# SCH_SHOC.net
KiCad netlist of a schematic drawn in EasyEDA
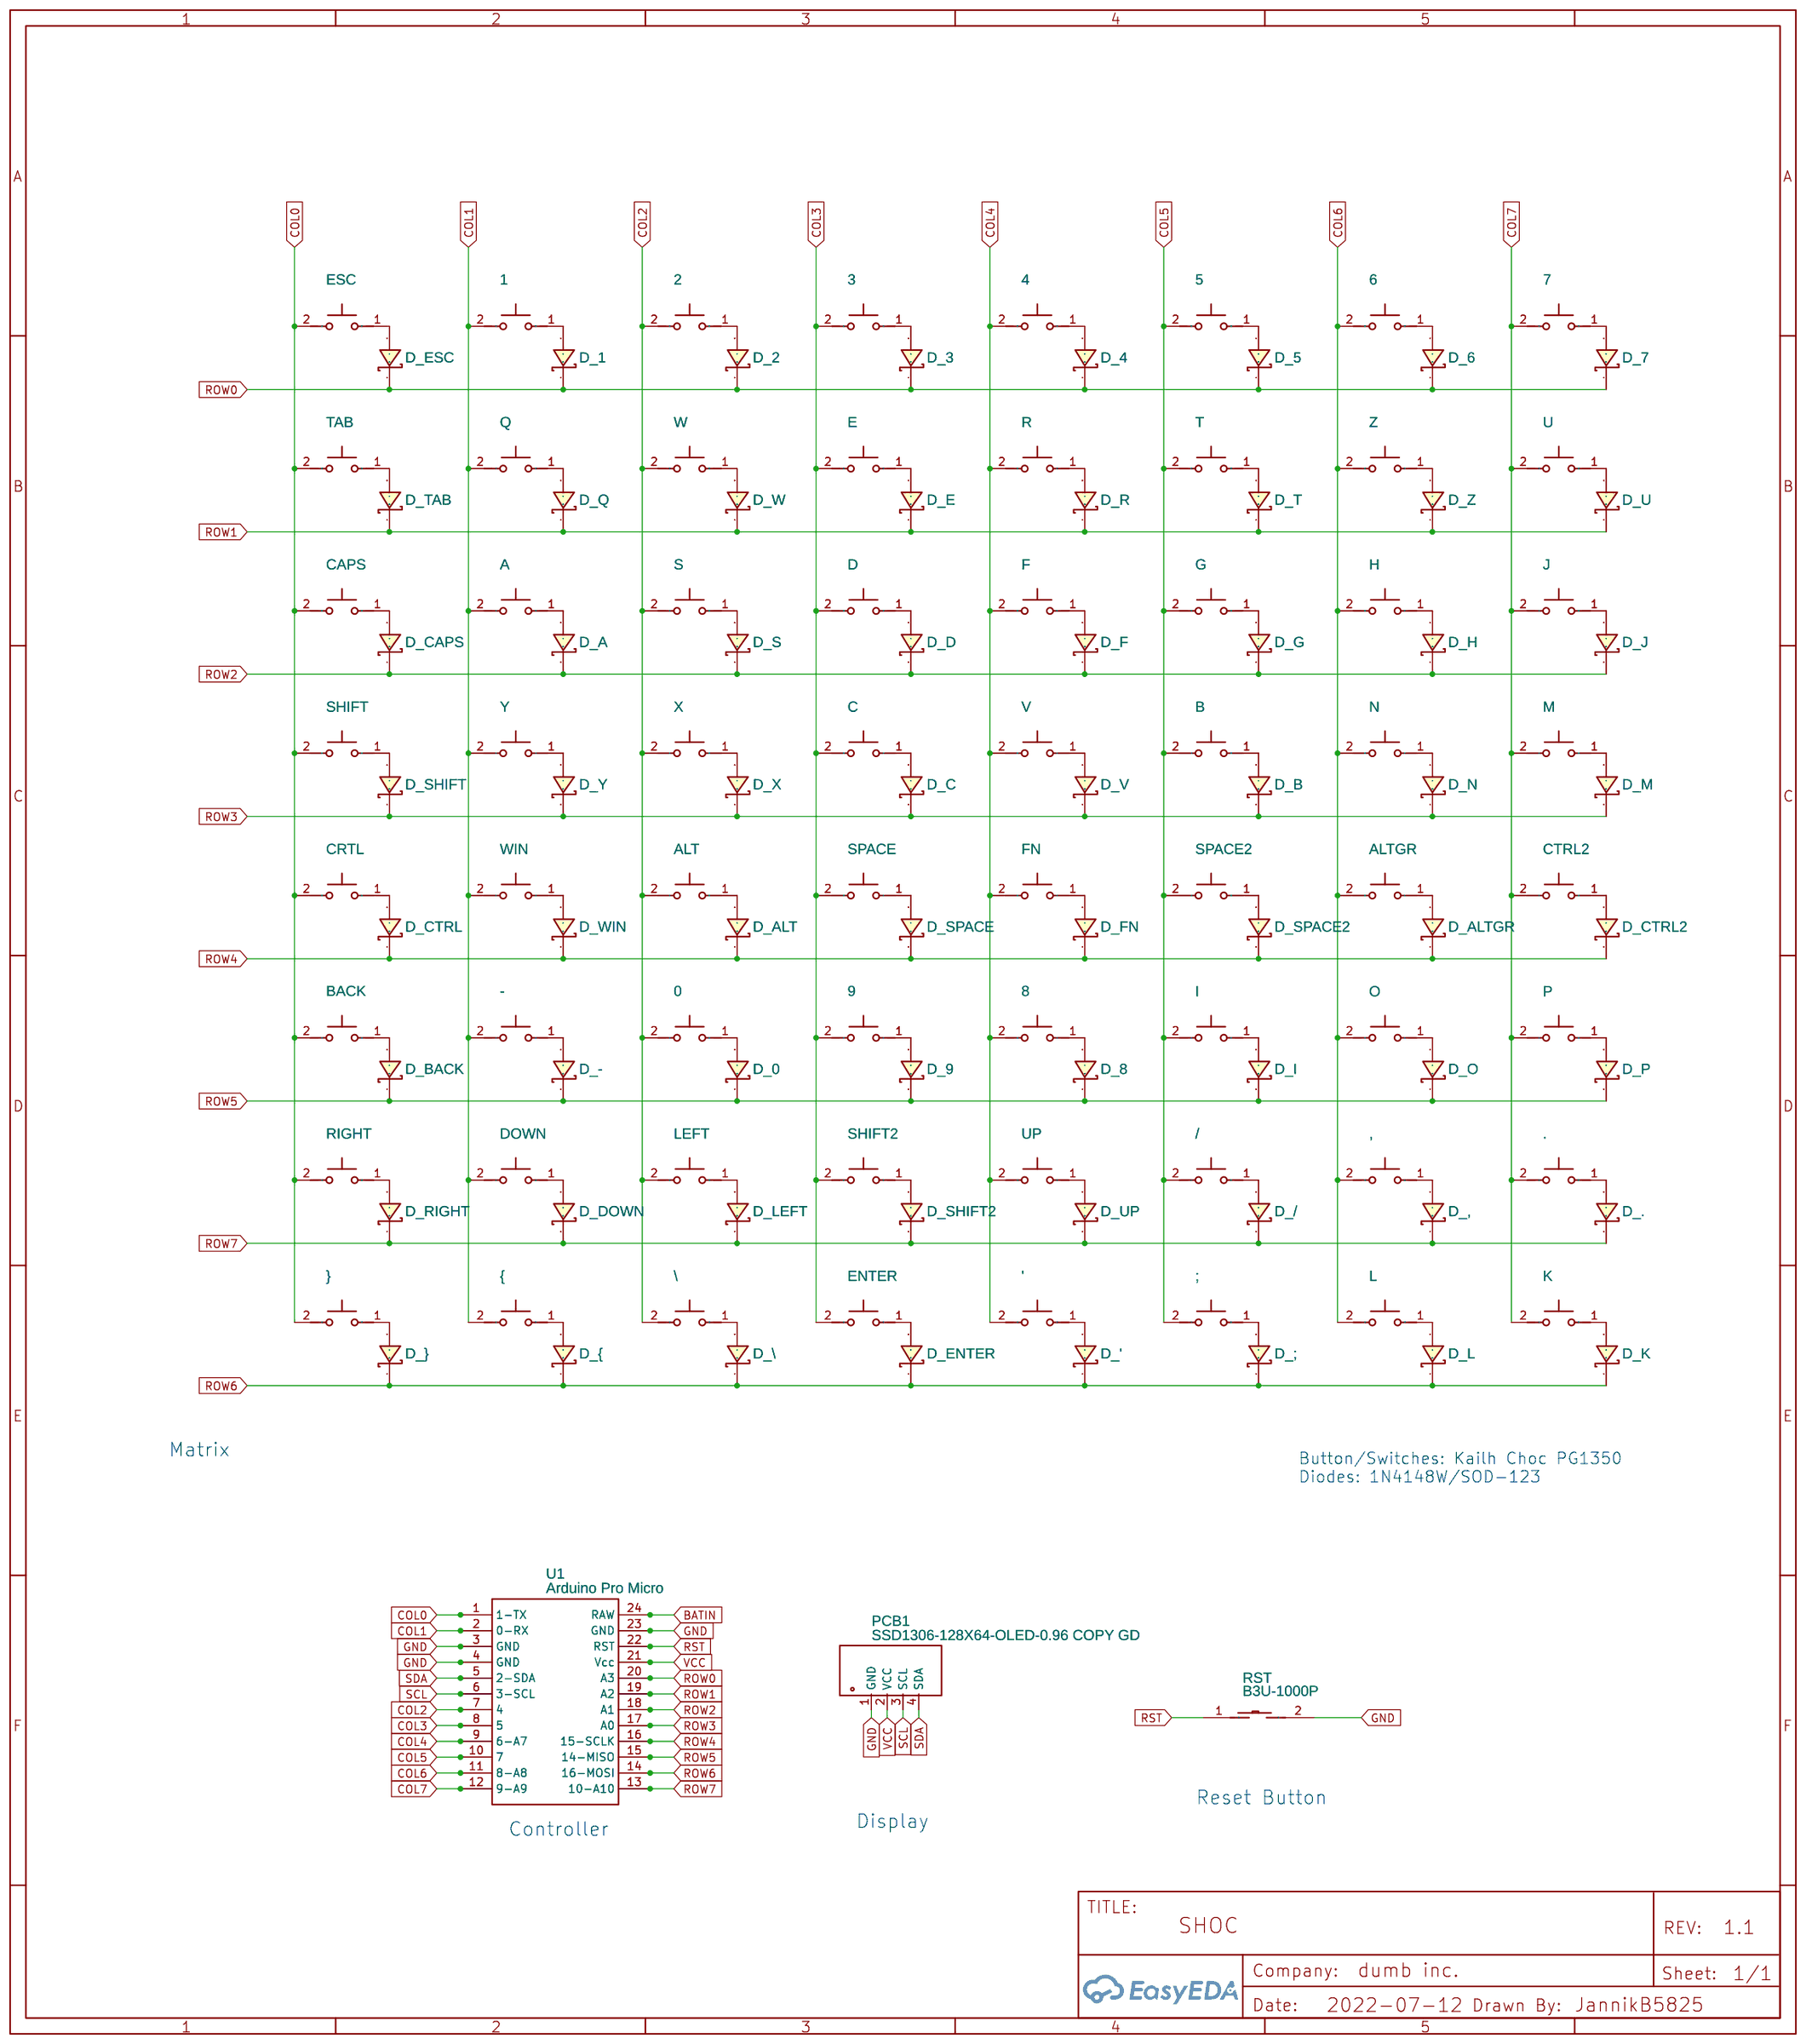
[diagram p0: schematic sheet]

(export (version "E")
  (design (tool "Eeschema 10.0.6"))
  (components
    (comp (ref "'")
      (value "PG1350")
      (fields
        (field (name "BOM_Manufacturer Part") "CPG135001D02")
        (field (name "BOM_Supplier Part") "C400230")
      )
      (libsource (lib "") (part "PG1350_35"))
    )
    (comp (ref ",")
      (value "PG1350")
      (fields
        (field (name "BOM_Manufacturer Part") "CPG135001D02")
        (field (name "BOM_Supplier Part") "C400230")
      )
      (libsource (lib "") (part "PG1350_47"))
    )
    (comp (ref "-")
      (value "PG1350")
      (fields
        (field (name "BOM_Manufacturer Part") "CPG135001D02")
        (field (name "BOM_Supplier Part") "C400230")
      )
      (libsource (lib "") (part "PG1350_14"))
    )
    (comp (ref ".")
      (value "PG1350")
      (fields
        (field (name "BOM_Manufacturer Part") "CPG135001D02")
        (field (name "BOM_Supplier Part") "C400230")
      )
      (libsource (lib "") (part "PG1350_38"))
    )
    (comp (ref "/")
      (value "PG1350")
      (fields
        (field (name "BOM_Manufacturer Part") "CPG135001D02")
        (field (name "BOM_Supplier Part") "C400230")
      )
      (libsource (lib "") (part "PG1350_29"))
    )
    (comp (ref "0")
      (value "PG1350")
      (fields
        (field (name "BOM_Manufacturer Part") "CPG135001D02")
        (field (name "BOM_Supplier Part") "C400230")
      )
      (libsource (lib "") (part "PG1350_15"))
    )
    (comp (ref "1")
      (value "PG1350")
      (fields
        (field (name "BOM_Manufacturer Part") "CPG135001D02")
        (field (name "BOM_Supplier Part") "C400230")
      )
      (libsource (lib "") (part "PG1350_15"))
    )
    (comp (ref "2")
      (value "PG1350")
      (fields
        (field (name "BOM_Manufacturer Part") "CPG135001D02")
        (field (name "BOM_Supplier Part") "C400230")
      )
      (libsource (lib "") (part "PG1350_15"))
    )
    (comp (ref "3")
      (value "PG1350")
      (fields
        (field (name "BOM_Manufacturer Part") "CPG135001D02")
        (field (name "BOM_Supplier Part") "C400230")
      )
      (libsource (lib "") (part "PG1350_15"))
    )
    (comp (ref "4")
      (value "PG1350")
      (fields
        (field (name "BOM_Manufacturer Part") "CPG135001D02")
        (field (name "BOM_Supplier Part") "C400230")
      )
      (libsource (lib "") (part "PG1350_15"))
    )
    (comp (ref "5")
      (value "PG1350")
      (fields
        (field (name "BOM_Manufacturer Part") "CPG135001D02")
        (field (name "BOM_Supplier Part") "C400230")
      )
      (libsource (lib "") (part "PG1350_15"))
    )
    (comp (ref "6")
      (value "PG1350")
      (fields
        (field (name "BOM_Manufacturer Part") "CPG135001D02")
        (field (name "BOM_Supplier Part") "C400230")
      )
      (libsource (lib "") (part "PG1350_15"))
    )
    (comp (ref "7")
      (value "PG1350")
      (fields
        (field (name "BOM_Manufacturer Part") "CPG135001D02")
        (field (name "BOM_Supplier Part") "C400230")
      )
      (libsource (lib "") (part "PG1350_15"))
    )
    (comp (ref "8")
      (value "PG1350")
      (fields
        (field (name "BOM_Manufacturer Part") "CPG135001D02")
        (field (name "BOM_Supplier Part") "C400230")
      )
      (libsource (lib "") (part "PG1350_15"))
    )
    (comp (ref "9")
      (value "PG1350")
      (fields
        (field (name "BOM_Manufacturer Part") "CPG135001D02")
        (field (name "BOM_Supplier Part") "C400230")
      )
      (libsource (lib "") (part "PG1350_15"))
    )
    (comp (ref ";")
      (value "PG1350")
      (fields
        (field (name "BOM_Manufacturer Part") "CPG135001D02")
        (field (name "BOM_Supplier Part") "C400230")
      )
      (libsource (lib "") (part "PG1350_20"))
    )
    (comp (ref "A")
      (value "PG1350")
      (fields (field (name "BOM_Manufacturer Part") "?"))
      (libsource (lib "") (part "Unknown_205_-1510"))
    )
    (comp (ref "ALT")
      (value "PG1350")
      (fields
        (field (name "BOM_Manufacturer Part") "CPG135001D02")
        (field (name "BOM_Supplier Part") "C400230")
      )
      (libsource (lib "") (part "PG1350_33"))
    )
    (comp (ref "ALTGR")
      (value "PG1350")
      (fields
        (field (name "BOM_Manufacturer Part") "CPG135001D02")
        (field (name "BOM_Supplier Part") "C400230")
      )
      (libsource (lib "") (part "PG1350_24"))
    )
    (comp (ref "B")
      (value "PG1350")
      (fields
        (field (name "BOM_Manufacturer Part") "CPG135001D02")
        (field (name "BOM_Supplier Part") "C400230")
      )
      (libsource (lib "") (part "PG1350_31"))
    )
    (comp (ref "BACK")
      (value "PG1350")
      (fields
        (field (name "BOM_Manufacturer Part") "CPG135001D02")
        (field (name "BOM_Supplier Part") "C400230")
      )
      (libsource (lib "") (part "PG1350_18"))
    )
    (comp (ref "C")
      (value "PG1350")
      (fields
        (field (name "BOM_Manufacturer Part") "CPG135001D02")
        (field (name "BOM_Supplier Part") "C400230")
      )
      (libsource (lib "") (part "PG1350"))
    )
    (comp (ref "CAPS")
      (value "PG1350")
      (fields
        (field (name "BOM_Manufacturer Part") "CPG135001D02")
        (field (name "BOM_Supplier Part") "C400230")
      )
      (libsource (lib "") (part "PG1350_9"))
    )
    (comp (ref "CRTL")
      (value "PG1350")
      (fields
        (field (name "BOM_Manufacturer Part") "CPG135001D02")
        (field (name "BOM_Supplier Part") "C400230")
      )
      (libsource (lib "") (part "PG1350_19"))
    )
    (comp (ref "CTRL2")
      (value "PG1350")
      (fields
        (field (name "BOM_Manufacturer Part") "CPG135001D02")
        (field (name "BOM_Supplier Part") "C400230")
      )
      (libsource (lib "") (part "PG1350_41"))
    )
    (comp (ref "D")
      (value "PG1350")
      (fields
        (field (name "BOM_Manufacturer Part") "CPG135001D02")
        (field (name "BOM_Supplier Part") "C400230")
      )
      (libsource (lib "") (part "PG1350_8"))
    )
    (comp (ref "DOWN")
      (value "PG1350")
      (fields
        (field (name "BOM_Manufacturer Part") "CPG135001D02")
        (field (name "BOM_Supplier Part") "C400230")
      )
      (libsource (lib "") (part "PG1350_30"))
    )
    (comp (ref "D_'")
      (value "MBR2H200SFT3G")
      (fields (field (name "BOM_Supplier Part") "MBR2H200SFT3GOSCT-ND"))
      (libsource (lib "") (part "MBR2H200SFT3G_51"))
    )
    (comp (ref "D_,")
      (value "MBR2H200SFT3G")
      (fields (field (name "BOM_Supplier Part") "MBR2H200SFT3GOSCT-ND"))
      (libsource (lib "") (part "MBR2H200SFT3G_27"))
    )
    (comp (ref "D_-")
      (value "MBR2H200SFT3G")
      (fields (field (name "BOM_Supplier Part") "MBR2H200SFT3GOSCT-ND"))
      (libsource (lib "") (part "MBR2H200SFT3G_3"))
    )
    (comp (ref "D_.")
      (value "MBR2H200SFT3G")
      (fields (field (name "BOM_Supplier Part") "MBR2H200SFT3GOSCT-ND"))
      (libsource (lib "") (part "MBR2H200SFT3G_7"))
    )
    (comp (ref "D_/")
      (value "MBR2H200SFT3G")
      (fields (field (name "BOM_Supplier Part") "MBR2H200SFT3GOSCT-ND"))
      (libsource (lib "") (part "MBR2H200SFT3G_31"))
    )
    (comp (ref "D_0")
      (value "MBR2H200SFT3G")
      (fields (field (name "BOM_Supplier Part") "MBR2H200SFT3GOSCT-ND"))
      (libsource (lib "") (part "MBR2H200SFT3G_8"))
    )
    (comp (ref "D_1")
      (value "MBR2H200SFT3G")
      (fields (field (name "BOM_Supplier Part") "MBR2H200SFT3GOSCT-ND"))
      (libsource (lib "") (part "MBR2H200SFT3G_8"))
    )
    (comp (ref "D_2")
      (value "MBR2H200SFT3G")
      (fields (field (name "BOM_Supplier Part") "MBR2H200SFT3GOSCT-ND"))
      (libsource (lib "") (part "MBR2H200SFT3G_8"))
    )
    (comp (ref "D_3")
      (value "MBR2H200SFT3G")
      (fields (field (name "BOM_Supplier Part") "MBR2H200SFT3GOSCT-ND"))
      (libsource (lib "") (part "MBR2H200SFT3G_8"))
    )
    (comp (ref "D_4")
      (value "MBR2H200SFT3G")
      (fields (field (name "BOM_Supplier Part") "MBR2H200SFT3GOSCT-ND"))
      (libsource (lib "") (part "MBR2H200SFT3G_8"))
    )
    (comp (ref "D_5")
      (value "MBR2H200SFT3G")
      (fields (field (name "BOM_Supplier Part") "MBR2H200SFT3GOSCT-ND"))
      (libsource (lib "") (part "MBR2H200SFT3G_8"))
    )
    (comp (ref "D_6")
      (value "MBR2H200SFT3G")
      (fields (field (name "BOM_Supplier Part") "MBR2H200SFT3GOSCT-ND"))
      (libsource (lib "") (part "MBR2H200SFT3G_8"))
    )
    (comp (ref "D_7")
      (value "MBR2H200SFT3G")
      (fields (field (name "BOM_Supplier Part") "MBR2H200SFT3GOSCT-ND"))
      (libsource (lib "") (part "MBR2H200SFT3G_8"))
    )
    (comp (ref "D_8")
      (value "MBR2H200SFT3G")
      (fields (field (name "BOM_Supplier Part") "MBR2H200SFT3GOSCT-ND"))
      (libsource (lib "") (part "MBR2H200SFT3G_8"))
    )
    (comp (ref "D_9")
      (value "MBR2H200SFT3G")
      (fields (field (name "BOM_Supplier Part") "MBR2H200SFT3GOSCT-ND"))
      (libsource (lib "") (part "MBR2H200SFT3G_8"))
    )
    (comp (ref "D_;")
      (value "MBR2H200SFT3G")
      (fields (field (name "BOM_Supplier Part") "MBR2H200SFT3GOSCT-ND"))
      (libsource (lib "") (part "MBR2H200SFT3G_13"))
    )
    (comp (ref "D_A")
      (value "MBR2H200SFT3G")
      (fields (field (name "BOM_Supplier Part") "MBR2H200SFT3GOSCT-ND"))
      (libsource (lib "") (part "MBR2H200SFT3G_44"))
    )
    (comp (ref "D_ALT")
      (value "MBR2H200SFT3G")
      (fields (field (name "BOM_Supplier Part") "MBR2H200SFT3GOSCT-ND"))
      (libsource (lib "") (part "MBR2H200SFT3G_21"))
    )
    (comp (ref "D_ALTGR")
      (value "MBR2H200SFT3G")
      (fields (field (name "BOM_Supplier Part") "MBR2H200SFT3GOSCT-ND"))
      (libsource (lib "") (part "MBR2H200SFT3G_42"))
    )
    (comp (ref "D_B")
      (value "MBR2H200SFT3G")
      (fields (field (name "BOM_Supplier Part") "MBR2H200SFT3GOSCT-ND"))
      (libsource (lib "") (part "MBR2H200SFT3G_18"))
    )
    (comp (ref "D_BACK")
      (value "MBR2H200SFT3G")
      (fields (field (name "BOM_Supplier Part") "MBR2H200SFT3GOSCT-ND"))
      (libsource (lib "") (part "MBR2H200SFT3G_12"))
    )
    (comp (ref "D_C")
      (value "MBR2H200SFT3G")
      (fields (field (name "BOM_Supplier Part") "MBR2H200SFT3GOSCT-ND"))
      (libsource (lib "") (part "MBR2H200SFT3G_19"))
    )
    (comp (ref "D_CAPS")
      (value "MBR2H200SFT3G")
      (fields (field (name "BOM_Supplier Part") "MBR2H200SFT3GOSCT-ND"))
      (libsource (lib "") (part "MBR2H200SFT3G_24"))
    )
    (comp (ref "D_CTRL")
      (value "MBR2H200SFT3G")
      (fields (field (name "BOM_Supplier Part") "MBR2H200SFT3GOSCT-ND"))
      (libsource (lib "") (part "MBR2H200SFT3G_22"))
    )
    (comp (ref "D_CTRL2")
      (value "MBR2H200SFT3G")
      (fields (field (name "BOM_Supplier Part") "MBR2H200SFT3GOSCT-ND"))
      (libsource (lib "") (part "MBR2H200SFT3G_22"))
    )
    (comp (ref "D_D")
      (value "MBR2H200SFT3G")
      (fields (field (name "BOM_Supplier Part") "MBR2H200SFT3GOSCT-ND"))
      (libsource (lib "") (part "MBR2H200SFT3G_23"))
    )
    (comp (ref "D_DOWN")
      (value "MBR2H200SFT3G")
      (fields (field (name "BOM_Supplier Part") "MBR2H200SFT3GOSCT-ND"))
      (libsource (lib "") (part "MBR2H200SFT3G_36"))
    )
    (comp (ref "D_E")
      (value "MBR2H200SFT3G")
      (fields (field (name "BOM_Supplier Part") "MBR2H200SFT3GOSCT-ND"))
      (libsource (lib "") (part "MBR2H200SFT3G_45"))
    )
    (comp (ref "D_ENTER")
      (value "MBR2H200SFT3G")
      (fields (field (name "BOM_Supplier Part") "MBR2H200SFT3GOSCT-ND"))
      (libsource (lib "") (part "MBR2H200SFT3G_41"))
    )
    (comp (ref "D_ESC")
      (value "MBR2H200SFT3G")
      (fields (field (name "BOM_Supplier Part") "MBR2H200SFT3GOSCT-ND"))
      (libsource (lib "") (part "MBR2H200SFT3G_6"))
    )
    (comp (ref "D_F")
      (value "MBR2H200SFT3G")
      (fields (field (name "BOM_Supplier Part") "MBR2H200SFT3GOSCT-ND"))
      (libsource (lib "") (part "MBR2H200SFT3G_34"))
    )
    (comp (ref "D_FN")
      (value "MBR2H200SFT3G")
      (fields (field (name "BOM_Supplier Part") "MBR2H200SFT3GOSCT-ND"))
      (libsource (lib "") (part "MBR2H200SFT3G_26"))
    )
    (comp (ref "D_G")
      (value "MBR2H200SFT3G")
      (fields (field (name "BOM_Supplier Part") "MBR2H200SFT3GOSCT-ND"))
      (libsource (lib "") (part "MBR2H200SFT3G_16"))
    )
    (comp (ref "D_H")
      (value "MBR2H200SFT3G")
      (fields (field (name "BOM_Supplier Part") "MBR2H200SFT3GOSCT-ND"))
      (libsource (lib "") (part "MBR2H200SFT3G_43"))
    )
    (comp (ref "D_I")
      (value "MBR2H200SFT3G")
      (fields (field (name "BOM_Supplier Part") "MBR2H200SFT3GOSCT-ND"))
      (libsource (lib "") (part "MBR2H200SFT3G_10"))
    )
    (comp (ref "D_J")
      (value "MBR2H200SFT3G")
      (fields (field (name "BOM_Supplier Part") "MBR2H200SFT3GOSCT-ND"))
      (libsource (lib "") (part "MBR2H200SFT3G_15"))
    )
    (comp (ref "D_K")
      (value "MBR2H200SFT3G")
      (fields (field (name "BOM_Supplier Part") "MBR2H200SFT3GOSCT-ND"))
      (libsource (lib "") (part "MBR2H200SFT3G_37"))
    )
    (comp (ref "D_L")
      (value "MBR2H200SFT3G")
      (fields (field (name "BOM_Supplier Part") "MBR2H200SFT3GOSCT-ND"))
      (libsource (lib "") (part "MBR2H200SFT3G_20"))
    )
    (comp (ref "D_LEFT")
      (value "MBR2H200SFT3G")
      (fields (field (name "BOM_Supplier Part") "MBR2H200SFT3GOSCT-ND"))
      (libsource (lib "") (part "MBR2H200SFT3G_48"))
    )
    (comp (ref "D_M")
      (value "MBR2H200SFT3G")
      (fields (field (name "BOM_Supplier Part") "MBR2H200SFT3GOSCT-ND"))
      (libsource (lib "") (part "MBR2H200SFT3G_33"))
    )
    (comp (ref "D_N")
      (value "MBR2H200SFT3G")
      (fields (field (name "BOM_Supplier Part") "MBR2H200SFT3GOSCT-ND"))
      (libsource (lib "") (part "MBR2H200SFT3G_47"))
    )
    (comp (ref "D_O")
      (value "MBR2H200SFT3G")
      (fields (field (name "BOM_Supplier Part") "MBR2H200SFT3GOSCT-ND"))
      (libsource (lib "") (part "MBR2H200SFT3G_4"))
    )
    (comp (ref "D_P")
      (value "MBR2H200SFT3G")
      (fields (field (name "BOM_Supplier Part") "MBR2H200SFT3GOSCT-ND"))
      (libsource (lib "") (part "MBR2H200SFT3G_49"))
    )
    (comp (ref "D_Q")
      (value "MBR2H200SFT3G")
      (fields (field (name "BOM_Supplier Part") "MBR2H200SFT3GOSCT-ND"))
      (libsource (lib "") (part "MBR2H200SFT3G_11"))
    )
    (comp (ref "D_R")
      (value "MBR2H200SFT3G")
      (fields (field (name "BOM_Supplier Part") "MBR2H200SFT3GOSCT-ND"))
      (libsource (lib "") (part "MBR2H200SFT3G_29"))
    )
    (comp (ref "D_RIGHT")
      (value "MBR2H200SFT3G")
      (fields (field (name "BOM_Supplier Part") "MBR2H200SFT3GOSCT-ND"))
      (libsource (lib "") (part "MBR2H200SFT3G_14"))
    )
    (comp (ref "D_S")
      (value "MBR2H200SFT3G")
      (fields (field (name "BOM_Supplier Part") "MBR2H200SFT3GOSCT-ND"))
      (libsource (lib "") (part "MBR2H200SFT3G_28"))
    )
    (comp (ref "D_SHIFT")
      (value "MBR2H200SFT3G")
      (fields (field (name "BOM_Supplier Part") "MBR2H200SFT3GOSCT-ND"))
      (libsource (lib "") (part "MBR2H200SFT3G_25"))
    )
    (comp (ref "D_SHIFT2")
      (value "MBR2H200SFT3G")
      (fields (field (name "BOM_Supplier Part") "MBR2H200SFT3GOSCT-ND"))
      (libsource (lib "") (part "MBR2H200SFT3G_25"))
    )
    (comp (ref "D_SPACE")
      (value "MBR2H200SFT3G")
      (fields (field (name "BOM_Supplier Part") "MBR2H200SFT3GOSCT-ND"))
      (libsource (lib "") (part "MBR2H200SFT3G_2"))
    )
    (comp (ref "D_SPACE2")
      (value "MBR2H200SFT3G")
      (fields (field (name "BOM_Supplier Part") "MBR2H200SFT3GOSCT-ND"))
      (libsource (lib "") (part "MBR2H200SFT3G_2"))
    )
    (comp (ref "D_T")
      (value "MBR2H200SFT3G")
      (fields (field (name "BOM_Supplier Part") "MBR2H200SFT3GOSCT-ND"))
      (libsource (lib "") (part "MBR2H200SFT3G_50"))
    )
    (comp (ref "D_TAB")
      (value "MBR2H200SFT3G")
      (fields (field (name "BOM_Supplier Part") "MBR2H200SFT3GOSCT-ND"))
      (libsource (lib "") (part "MBR2H200SFT3G_32"))
    )
    (comp (ref "D_U")
      (value "MBR2H200SFT3G")
      (fields (field (name "BOM_Supplier Part") "MBR2H200SFT3GOSCT-ND"))
      (libsource (lib "") (part "MBR2H200SFT3G_46"))
    )
    (comp (ref "D_UP")
      (value "MBR2H200SFT3G")
      (fields (field (name "BOM_Supplier Part") "MBR2H200SFT3GOSCT-ND"))
      (libsource (lib "") (part "MBR2H200SFT3G_9"))
    )
    (comp (ref "D_V")
      (value "MBR2H200SFT3G")
      (fields (field (name "BOM_Supplier Part") "MBR2H200SFT3GOSCT-ND"))
      (libsource (lib "") (part "MBR2H200SFT3G_17"))
    )
    (comp (ref "D_W")
      (value "MBR2H200SFT3G")
      (fields (field (name "BOM_Supplier Part") "MBR2H200SFT3GOSCT-ND"))
      (libsource (lib "") (part "MBR2H200SFT3G"))
    )
    (comp (ref "D_WIN")
      (value "MBR2H200SFT3G")
      (fields (field (name "BOM_Supplier Part") "MBR2H200SFT3GOSCT-ND"))
      (libsource (lib "") (part "MBR2H200SFT3G_5"))
    )
    (comp (ref "D_X")
      (value "MBR2H200SFT3G")
      (fields (field (name "BOM_Supplier Part") "MBR2H200SFT3GOSCT-ND"))
      (libsource (lib "") (part "MBR2H200SFT3G_35"))
    )
    (comp (ref "D_Y")
      (value "MBR2H200SFT3G")
      (fields (field (name "BOM_Supplier Part") "MBR2H200SFT3GOSCT-ND"))
      (libsource (lib "") (part "MBR2H200SFT3G_40"))
    )
    (comp (ref "D_Z")
      (value "MBR2H200SFT3G")
      (fields (field (name "BOM_Supplier Part") "MBR2H200SFT3GOSCT-ND"))
      (libsource (lib "") (part "MBR2H200SFT3G_39"))
    )
    (comp (ref "D_\\")
      (value "MBR2H200SFT3G")
      (fields (field (name "BOM_Supplier Part") "MBR2H200SFT3GOSCT-ND"))
      (libsource (lib "") (part "MBR2H200SFT3G_30"))
    )
    (comp (ref "D_{")
      (value "MBR2H200SFT3G")
      (fields (field (name "BOM_Supplier Part") "MBR2H200SFT3GOSCT-ND"))
      (libsource (lib "") (part "MBR2H200SFT3G_38"))
    )
    (comp (ref "D_}")
      (value "MBR2H200SFT3G")
      (fields (field (name "BOM_Supplier Part") "MBR2H200SFT3GOSCT-ND"))
      (libsource (lib "") (part "MBR2H200SFT3G_1"))
    )
    (comp (ref "E")
      (value "PG1350")
      (fields
        (field (name "BOM_Manufacturer Part") "CPG135001D02")
        (field (name "BOM_Supplier Part") "C400230")
      )
      (libsource (lib "") (part "PG1350_23"))
    )
    (comp (ref "ENTER")
      (value "PG1350")
      (fields
        (field (name "BOM_Manufacturer Part") "CPG135001D02")
        (field (name "BOM_Supplier Part") "C400230")
      )
      (libsource (lib "") (part "PG1350_50"))
    )
    (comp (ref "ESC")
      (value "PG1350")
      (fields
        (field (name "BOM_Manufacturer Part") "CPG135001D02")
        (field (name "BOM_Supplier Part") "C400230")
      )
      (libsource (lib "") (part "PG1350_17"))
    )
    (comp (ref "F")
      (value "PG1350")
      (fields
        (field (name "BOM_Manufacturer Part") "CPG135001D02")
        (field (name "BOM_Supplier Part") "C400230")
      )
      (libsource (lib "") (part "PG1350_11"))
    )
    (comp (ref "FN")
      (value "PG1350")
      (fields
        (field (name "BOM_Manufacturer Part") "CPG135001D02")
        (field (name "BOM_Supplier Part") "C400230")
      )
      (libsource (lib "") (part "PG1350_22"))
    )
    (comp (ref "G")
      (value "PG1350")
      (fields
        (field (name "BOM_Manufacturer Part") "CPG135001D02")
        (field (name "BOM_Supplier Part") "C400230")
      )
      (libsource (lib "") (part "PG1350_52"))
    )
    (comp (ref "H")
      (value "PG1350")
      (fields
        (field (name "BOM_Manufacturer Part") "CPG135001D02")
        (field (name "BOM_Supplier Part") "C400230")
      )
      (libsource (lib "") (part "PG1350_51"))
    )
    (comp (ref "I")
      (value "PG1350")
      (fields
        (field (name "BOM_Manufacturer Part") "CPG135001D02")
        (field (name "BOM_Supplier Part") "C400230")
      )
      (libsource (lib "") (part "PG1350_7"))
    )
    (comp (ref "J")
      (value "PG1350")
      (fields
        (field (name "BOM_Manufacturer Part") "CPG135001D02")
        (field (name "BOM_Supplier Part") "C400230")
      )
      (libsource (lib "") (part "PG1350_12"))
    )
    (comp (ref "K")
      (value "PG1350")
      (fields
        (field (name "BOM_Manufacturer Part") "CPG135001D02")
        (field (name "BOM_Supplier Part") "C400230")
      )
      (libsource (lib "") (part "PG1350_46"))
    )
    (comp (ref "L")
      (value "PG1350")
      (fields
        (field (name "BOM_Manufacturer Part") "CPG135001D02")
        (field (name "BOM_Supplier Part") "C400230")
      )
      (libsource (lib "") (part "PG1350_6"))
    )
    (comp (ref "LEFT")
      (value "PG1350")
      (fields
        (field (name "BOM_Manufacturer Part") "CPG135001D02")
        (field (name "BOM_Supplier Part") "C400230")
      )
      (libsource (lib "") (part "PG1350_2"))
    )
    (comp (ref "M")
      (value "PG1350")
      (fields
        (field (name "BOM_Manufacturer Part") "CPG135001D02")
        (field (name "BOM_Supplier Part") "C400230")
      )
      (libsource (lib "") (part "PG1350_28"))
    )
    (comp (ref "N")
      (value "PG1350")
      (fields
        (field (name "BOM_Manufacturer Part") "CPG135001D02")
        (field (name "BOM_Supplier Part") "C400230")
      )
      (libsource (lib "") (part "PG1350_10"))
    )
    (comp (ref "O")
      (value "PG1350")
      (fields
        (field (name "BOM_Manufacturer Part") "CPG135001D02")
        (field (name "BOM_Supplier Part") "C400230")
      )
      (libsource (lib "") (part "PG1350_26"))
    )
    (comp (ref "P")
      (value "PG1350")
      (fields
        (field (name "BOM_Manufacturer Part") "CPG135001D02")
        (field (name "BOM_Supplier Part") "C400230")
      )
      (libsource (lib "") (part "PG1350_42"))
    )
    (comp (ref "PCB1")
      (value "SSD1306-128X64-OLED-0.96 COPY GD")
      (libsource (lib "") (part "SSD1306-128X64-OLED-0.96 COPY GD"))
    )
    (comp (ref "Q")
      (value "PG1350")
      (fields
        (field (name "BOM_Manufacturer Part") "CPG135001D02")
        (field (name "BOM_Supplier Part") "C400230")
      )
      (libsource (lib "") (part "PG1350_49"))
    )
    (comp (ref "R")
      (value "PG1350")
      (fields
        (field (name "BOM_Manufacturer Part") "CPG135001D02")
        (field (name "BOM_Supplier Part") "C400230")
      )
      (libsource (lib "") (part "PG1350_36"))
    )
    (comp (ref "RIGHT")
      (value "PG1350")
      (fields
        (field (name "BOM_Manufacturer Part") "CPG135001D02")
        (field (name "BOM_Supplier Part") "C400230")
      )
      (libsource (lib "") (part "PG1350_27"))
    )
    (comp (ref "RST")
      (value "B3U-1000P")
      (fields (field (name "BOM_Supplier Part") "C231329"))
      (libsource (lib "") (part "B3U-1000P"))
    )
    (comp (ref "S")
      (value "PG1350")
      (fields
        (field (name "BOM_Manufacturer Part") "CPG135001D02")
        (field (name "BOM_Supplier Part") "C400230")
      )
      (libsource (lib "") (part "PG1350_43"))
    )
    (comp (ref "SHIFT")
      (value "PG1350")
      (fields
        (field (name "BOM_Manufacturer Part") "CPG135001D02")
        (field (name "BOM_Supplier Part") "C400230")
      )
      (libsource (lib "") (part "PG1350_48"))
    )
    (comp (ref "SHIFT2")
      (value "PG1350")
      (fields
        (field (name "BOM_Manufacturer Part") "CPG135001D02")
        (field (name "BOM_Supplier Part") "C400230")
      )
      (libsource (lib "") (part "PG1350_48"))
    )
    (comp (ref "SPACE")
      (value "PG1350")
      (fields
        (field (name "BOM_Manufacturer Part") "CPG135001D02")
        (field (name "BOM_Supplier Part") "C400230")
      )
      (libsource (lib "") (part "PG1350_1"))
    )
    (comp (ref "SPACE2")
      (value "PG1350")
      (fields
        (field (name "BOM_Manufacturer Part") "CPG135001D02")
        (field (name "BOM_Supplier Part") "C400230")
      )
      (libsource (lib "") (part "PG1350_1"))
    )
    (comp (ref "T")
      (value "PG1350")
      (fields
        (field (name "BOM_Manufacturer Part") "CPG135001D02")
        (field (name "BOM_Supplier Part") "C400230")
      )
      (libsource (lib "") (part "PG1350_25"))
    )
    (comp (ref "TAB")
      (value "PG1350")
      (fields
        (field (name "BOM_Manufacturer Part") "CPG135001D02")
        (field (name "BOM_Supplier Part") "C400230")
      )
      (libsource (lib "") (part "PG1350_16"))
    )
    (comp (ref "U")
      (value "PG1350")
      (fields
        (field (name "BOM_Manufacturer Part") "CPG135001D02")
        (field (name "BOM_Supplier Part") "C400230")
      )
      (libsource (lib "") (part "PG1350_21"))
    )
    (comp (ref "U1") (value "Arduino Pro Micro") (libsource (lib "") (part "Arduino Pro Micro")))
    (comp (ref "UP")
      (value "PG1350")
      (fields
        (field (name "BOM_Manufacturer Part") "CPG135001D02")
        (field (name "BOM_Supplier Part") "C400230")
      )
      (libsource (lib "") (part "PG1350_3"))
    )
    (comp (ref "V")
      (value "PG1350")
      (fields
        (field (name "BOM_Manufacturer Part") "CPG135001D02")
        (field (name "BOM_Supplier Part") "C400230")
      )
      (libsource (lib "") (part "PG1350_40"))
    )
    (comp (ref "W")
      (value "PG1350")
      (fields
        (field (name "BOM_Manufacturer Part") "CPG135001D02")
        (field (name "BOM_Supplier Part") "C400230")
      )
      (libsource (lib "") (part "PG1350_39"))
    )
    (comp (ref "WIN")
      (value "PG1350")
      (fields
        (field (name "BOM_Manufacturer Part") "CPG135001D02")
        (field (name "BOM_Supplier Part") "C400230")
      )
      (libsource (lib "") (part "PG1350_4"))
    )
    (comp (ref "X")
      (value "PG1350")
      (fields
        (field (name "BOM_Manufacturer Part") "CPG135001D02")
        (field (name "BOM_Supplier Part") "C400230")
      )
      (libsource (lib "") (part "PG1350_32"))
    )
    (comp (ref "Y")
      (value "PG1350")
      (fields
        (field (name "BOM_Manufacturer Part") "CPG135001D02")
        (field (name "BOM_Supplier Part") "C400230")
      )
      (libsource (lib "") (part "PG1350_44"))
    )
    (comp (ref "Z")
      (value "PG1350")
      (fields
        (field (name "BOM_Manufacturer Part") "CPG135001D02")
        (field (name "BOM_Supplier Part") "C400230")
      )
      (libsource (lib "") (part "PG1350_37"))
    )
    (comp (ref "\\")
      (value "PG1350")
      (fields
        (field (name "BOM_Manufacturer Part") "CPG135001D02")
        (field (name "BOM_Supplier Part") "C400230")
      )
      (libsource (lib "") (part "PG1350_45"))
    )
    (comp (ref "{")
      (value "PG1350")
      (fields
        (field (name "BOM_Manufacturer Part") "CPG135001D02")
        (field (name "BOM_Supplier Part") "C400230")
      )
      (libsource (lib "") (part "PG1350_13"))
    )
    (comp (ref "}")
      (value "PG1350")
      (fields
        (field (name "BOM_Manufacturer Part") "CPG135001D02")
        (field (name "BOM_Supplier Part") "C400230")
      )
      (libsource (lib "") (part "PG1350_34"))
    )
  )
  (nets
    (net (code "1") (name "BATIN") (class "Default")
      (node (ref "U1") (pin "24") (pinfunction "RAW_24") (pintype "unspecified"))
    )
    (net (code "2") (name "COL0") (class "Default")
      (node (ref "BACK") (pin "2") (pinfunction "1_2") (pintype "unspecified"))
      (node (ref "CAPS") (pin "2") (pinfunction "1_2") (pintype "unspecified"))
      (node (ref "CRTL") (pin "2") (pinfunction "1_2") (pintype "unspecified"))
      (node (ref "ESC") (pin "2") (pinfunction "1_2") (pintype "unspecified"))
      (node (ref "RIGHT") (pin "2") (pinfunction "1_2") (pintype "unspecified"))
      (node (ref "SHIFT") (pin "2") (pinfunction "1_2") (pintype "unspecified"))
      (node (ref "TAB") (pin "2") (pinfunction "1_2") (pintype "unspecified"))
      (node (ref "U1") (pin "1") (pinfunction "1-TX_1") (pintype "unspecified"))
      (node (ref "}") (pin "2") (pinfunction "1_2") (pintype "unspecified"))
    )
    (net (code "3") (name "COL1") (class "Default")
      (node (ref "-") (pin "2") (pinfunction "1_2") (pintype "unspecified"))
      (node (ref "1") (pin "2") (pinfunction "1_2") (pintype "unspecified"))
      (node (ref "A") (pin "2") (pinfunction "1_2") (pintype "unspecified"))
      (node (ref "DOWN") (pin "2") (pinfunction "1_2") (pintype "unspecified"))
      (node (ref "Q") (pin "2") (pinfunction "1_2") (pintype "unspecified"))
      (node (ref "U1") (pin "2") (pinfunction "0-RX_2") (pintype "unspecified"))
      (node (ref "WIN") (pin "2") (pinfunction "1_2") (pintype "unspecified"))
      (node (ref "Y") (pin "2") (pinfunction "1_2") (pintype "unspecified"))
      (node (ref "{") (pin "2") (pinfunction "1_2") (pintype "unspecified"))
    )
    (net (code "4") (name "COL2") (class "Default")
      (node (ref "0") (pin "2") (pinfunction "1_2") (pintype "unspecified"))
      (node (ref "2") (pin "2") (pinfunction "1_2") (pintype "unspecified"))
      (node (ref "ALT") (pin "2") (pinfunction "1_2") (pintype "unspecified"))
      (node (ref "LEFT") (pin "2") (pinfunction "1_2") (pintype "unspecified"))
      (node (ref "S") (pin "2") (pinfunction "1_2") (pintype "unspecified"))
      (node (ref "U1") (pin "7") (pinfunction "4_7") (pintype "unspecified"))
      (node (ref "W") (pin "2") (pinfunction "1_2") (pintype "unspecified"))
      (node (ref "X") (pin "2") (pinfunction "1_2") (pintype "unspecified"))
      (node (ref "\\") (pin "2") (pinfunction "1_2") (pintype "unspecified"))
    )
    (net (code "5") (name "COL3") (class "Default")
      (node (ref "3") (pin "2") (pinfunction "1_2") (pintype "unspecified"))
      (node (ref "9") (pin "2") (pinfunction "1_2") (pintype "unspecified"))
      (node (ref "C") (pin "2") (pinfunction "1_2") (pintype "unspecified"))
      (node (ref "D") (pin "2") (pinfunction "1_2") (pintype "unspecified"))
      (node (ref "E") (pin "2") (pinfunction "1_2") (pintype "unspecified"))
      (node (ref "ENTER") (pin "2") (pinfunction "1_2") (pintype "unspecified"))
      (node (ref "SHIFT2") (pin "2") (pinfunction "1_2") (pintype "unspecified"))
      (node (ref "SPACE") (pin "2") (pinfunction "1_2") (pintype "unspecified"))
      (node (ref "U1") (pin "8") (pinfunction "5_8") (pintype "unspecified"))
    )
    (net (code "6") (name "COL4") (class "Default")
      (node (ref "'") (pin "2") (pinfunction "1_2") (pintype "unspecified"))
      (node (ref "4") (pin "2") (pinfunction "1_2") (pintype "unspecified"))
      (node (ref "8") (pin "2") (pinfunction "1_2") (pintype "unspecified"))
      (node (ref "F") (pin "2") (pinfunction "1_2") (pintype "unspecified"))
      (node (ref "FN") (pin "2") (pinfunction "1_2") (pintype "unspecified"))
      (node (ref "R") (pin "2") (pinfunction "1_2") (pintype "unspecified"))
      (node (ref "U1") (pin "9") (pinfunction "6-A7_9") (pintype "unspecified"))
      (node (ref "UP") (pin "2") (pinfunction "1_2") (pintype "unspecified"))
      (node (ref "V") (pin "2") (pinfunction "1_2") (pintype "unspecified"))
    )
    (net (code "7") (name "COL5") (class "Default")
      (node (ref "/") (pin "2") (pinfunction "1_2") (pintype "unspecified"))
      (node (ref "5") (pin "2") (pinfunction "1_2") (pintype "unspecified"))
      (node (ref ";") (pin "2") (pinfunction "1_2") (pintype "unspecified"))
      (node (ref "B") (pin "2") (pinfunction "1_2") (pintype "unspecified"))
      (node (ref "G") (pin "2") (pinfunction "1_2") (pintype "unspecified"))
      (node (ref "I") (pin "2") (pinfunction "1_2") (pintype "unspecified"))
      (node (ref "SPACE2") (pin "2") (pinfunction "1_2") (pintype "unspecified"))
      (node (ref "T") (pin "2") (pinfunction "1_2") (pintype "unspecified"))
      (node (ref "U1") (pin "10") (pinfunction "7_10") (pintype "unspecified"))
    )
    (net (code "8") (name "COL6") (class "Default")
      (node (ref ",") (pin "2") (pinfunction "1_2") (pintype "unspecified"))
      (node (ref "6") (pin "2") (pinfunction "1_2") (pintype "unspecified"))
      (node (ref "ALTGR") (pin "2") (pinfunction "1_2") (pintype "unspecified"))
      (node (ref "H") (pin "2") (pinfunction "1_2") (pintype "unspecified"))
      (node (ref "L") (pin "2") (pinfunction "1_2") (pintype "unspecified"))
      (node (ref "N") (pin "2") (pinfunction "1_2") (pintype "unspecified"))
      (node (ref "O") (pin "2") (pinfunction "1_2") (pintype "unspecified"))
      (node (ref "U1") (pin "11") (pinfunction "8-A8_11") (pintype "unspecified"))
      (node (ref "Z") (pin "2") (pinfunction "1_2") (pintype "unspecified"))
    )
    (net (code "9") (name "COL7") (class "Default")
      (node (ref ".") (pin "2") (pinfunction "1_2") (pintype "unspecified"))
      (node (ref "7") (pin "2") (pinfunction "1_2") (pintype "unspecified"))
      (node (ref "CTRL2") (pin "2") (pinfunction "1_2") (pintype "unspecified"))
      (node (ref "J") (pin "2") (pinfunction "1_2") (pintype "unspecified"))
      (node (ref "K") (pin "2") (pinfunction "1_2") (pintype "unspecified"))
      (node (ref "M") (pin "2") (pinfunction "1_2") (pintype "unspecified"))
      (node (ref "P") (pin "2") (pinfunction "1_2") (pintype "unspecified"))
      (node (ref "U") (pin "2") (pinfunction "1_2") (pintype "unspecified"))
      (node (ref "U1") (pin "12") (pinfunction "9-A9_12") (pintype "unspecified"))
    )
    (net (code "10") (name "GND") (class "Default")
      (node (ref "PCB1") (pin "1") (pinfunction "GND_1") (pintype "input"))
      (node (ref "RST") (pin "2") (pinfunction "2_2") (pintype "unspecified"))
      (node (ref "U1") (pin "23") (pinfunction "GND_23") (pintype "unspecified"))
      (node (ref "U1") (pin "3") (pinfunction "GND_3") (pintype "unspecified"))
      (node (ref "U1") (pin "4") (pinfunction "GND_4") (pintype "unspecified"))
    )
    (net (code "11") (name "Net-('-2)") (class "Default")
      (node (ref "'") (pin "1") (pinfunction "2_1") (pintype "unspecified"))
      (node (ref "D_'") (pin "2") (pinfunction "A_2") (pintype "unspecified"))
    )
    (net (code "12") (name "Net-(,-2)") (class "Default")
      (node (ref ",") (pin "1") (pinfunction "2_1") (pintype "unspecified"))
      (node (ref "D_,") (pin "2") (pinfunction "A_2") (pintype "unspecified"))
    )
    (net (code "13") (name "Net-(--2)") (class "Default")
      (node (ref "-") (pin "1") (pinfunction "2_1") (pintype "unspecified"))
      (node (ref "D_-") (pin "2") (pinfunction "A_2") (pintype "unspecified"))
    )
    (net (code "14") (name "Net-(.-2)") (class "Default")
      (node (ref ".") (pin "1") (pinfunction "2_1") (pintype "unspecified"))
      (node (ref "D_.") (pin "2") (pinfunction "A_2") (pintype "unspecified"))
    )
    (net (code "15") (name "Net-(/-2)") (class "Default")
      (node (ref "/") (pin "1") (pinfunction "2_1") (pintype "unspecified"))
      (node (ref "D_/") (pin "2") (pinfunction "A_2") (pintype "unspecified"))
    )
    (net (code "16") (name "Net-(0-2)") (class "Default")
      (node (ref "0") (pin "1") (pinfunction "2_1") (pintype "unspecified"))
      (node (ref "D_0") (pin "2") (pinfunction "A_2") (pintype "unspecified"))
    )
    (net (code "17") (name "Net-(1-2)") (class "Default")
      (node (ref "1") (pin "1") (pinfunction "2_1") (pintype "unspecified"))
      (node (ref "D_1") (pin "2") (pinfunction "A_2") (pintype "unspecified"))
    )
    (net (code "18") (name "Net-(2-2)") (class "Default")
      (node (ref "2") (pin "1") (pinfunction "2_1") (pintype "unspecified"))
      (node (ref "D_2") (pin "2") (pinfunction "A_2") (pintype "unspecified"))
    )
    (net (code "19") (name "Net-(3-2)") (class "Default")
      (node (ref "3") (pin "1") (pinfunction "2_1") (pintype "unspecified"))
      (node (ref "D_3") (pin "2") (pinfunction "A_2") (pintype "unspecified"))
    )
    (net (code "20") (name "Net-(4-2)") (class "Default")
      (node (ref "4") (pin "1") (pinfunction "2_1") (pintype "unspecified"))
      (node (ref "D_4") (pin "2") (pinfunction "A_2") (pintype "unspecified"))
    )
    (net (code "21") (name "Net-(5-2)") (class "Default")
      (node (ref "5") (pin "1") (pinfunction "2_1") (pintype "unspecified"))
      (node (ref "D_5") (pin "2") (pinfunction "A_2") (pintype "unspecified"))
    )
    (net (code "22") (name "Net-(6-2)") (class "Default")
      (node (ref "6") (pin "1") (pinfunction "2_1") (pintype "unspecified"))
      (node (ref "D_6") (pin "2") (pinfunction "A_2") (pintype "unspecified"))
    )
    (net (code "23") (name "Net-(7-2)") (class "Default")
      (node (ref "7") (pin "1") (pinfunction "2_1") (pintype "unspecified"))
      (node (ref "D_7") (pin "2") (pinfunction "A_2") (pintype "unspecified"))
    )
    (net (code "24") (name "Net-(8-2)") (class "Default")
      (node (ref "8") (pin "1") (pinfunction "2_1") (pintype "unspecified"))
      (node (ref "D_8") (pin "2") (pinfunction "A_2") (pintype "unspecified"))
    )
    (net (code "25") (name "Net-(9-2)") (class "Default")
      (node (ref "9") (pin "1") (pinfunction "2_1") (pintype "unspecified"))
      (node (ref "D_9") (pin "2") (pinfunction "A_2") (pintype "unspecified"))
    )
    (net (code "26") (name "Net-(;-2)") (class "Default")
      (node (ref ";") (pin "1") (pinfunction "2_1") (pintype "unspecified"))
      (node (ref "D_;") (pin "2") (pinfunction "A_2") (pintype "unspecified"))
    )
    (net (code "27") (name "Net-(A-2)") (class "Default")
      (node (ref "A") (pin "1") (pinfunction "2_1") (pintype "unspecified"))
      (node (ref "D_A") (pin "2") (pinfunction "A_2") (pintype "unspecified"))
    )
    (net (code "28") (name "Net-(ALT-2)") (class "Default")
      (node (ref "ALT") (pin "1") (pinfunction "2_1") (pintype "unspecified"))
      (node (ref "D_ALT") (pin "2") (pinfunction "A_2") (pintype "unspecified"))
    )
    (net (code "29") (name "Net-(ALTGR-2)") (class "Default")
      (node (ref "ALTGR") (pin "1") (pinfunction "2_1") (pintype "unspecified"))
      (node (ref "D_ALTGR") (pin "2") (pinfunction "A_2") (pintype "unspecified"))
    )
    (net (code "30") (name "Net-(B-2)") (class "Default")
      (node (ref "B") (pin "1") (pinfunction "2_1") (pintype "unspecified"))
      (node (ref "D_B") (pin "2") (pinfunction "A_2") (pintype "unspecified"))
    )
    (net (code "31") (name "Net-(BACK-2)") (class "Default")
      (node (ref "BACK") (pin "1") (pinfunction "2_1") (pintype "unspecified"))
      (node (ref "D_BACK") (pin "2") (pinfunction "A_2") (pintype "unspecified"))
    )
    (net (code "32") (name "Net-(C-2)") (class "Default")
      (node (ref "C") (pin "1") (pinfunction "2_1") (pintype "unspecified"))
      (node (ref "D_C") (pin "2") (pinfunction "A_2") (pintype "unspecified"))
    )
    (net (code "33") (name "Net-(CAPS-2)") (class "Default")
      (node (ref "CAPS") (pin "1") (pinfunction "2_1") (pintype "unspecified"))
      (node (ref "D_CAPS") (pin "2") (pinfunction "A_2") (pintype "unspecified"))
    )
    (net (code "34") (name "Net-(CRTL-2)") (class "Default")
      (node (ref "CRTL") (pin "1") (pinfunction "2_1") (pintype "unspecified"))
      (node (ref "D_CTRL") (pin "2") (pinfunction "A_2") (pintype "unspecified"))
    )
    (net (code "35") (name "Net-(CTRL2-2)") (class "Default")
      (node (ref "CTRL2") (pin "1") (pinfunction "2_1") (pintype "unspecified"))
      (node (ref "D_CTRL2") (pin "2") (pinfunction "A_2") (pintype "unspecified"))
    )
    (net (code "36") (name "Net-(D-2)") (class "Default")
      (node (ref "D") (pin "1") (pinfunction "2_1") (pintype "unspecified"))
      (node (ref "D_D") (pin "2") (pinfunction "A_2") (pintype "unspecified"))
    )
    (net (code "37") (name "Net-(DOWN-2)") (class "Default")
      (node (ref "DOWN") (pin "1") (pinfunction "2_1") (pintype "unspecified"))
      (node (ref "D_DOWN") (pin "2") (pinfunction "A_2") (pintype "unspecified"))
    )
    (net (code "38") (name "Net-(D_E-A)") (class "Default")
      (node (ref "D_E") (pin "2") (pinfunction "A_2") (pintype "unspecified"))
      (node (ref "E") (pin "1") (pinfunction "2_1") (pintype "unspecified"))
    )
    (net (code "39") (name "Net-(D_ENTER-A)") (class "Default")
      (node (ref "D_ENTER") (pin "2") (pinfunction "A_2") (pintype "unspecified"))
      (node (ref "ENTER") (pin "1") (pinfunction "2_1") (pintype "unspecified"))
    )
    (net (code "40") (name "Net-(D_ESC-A)") (class "Default")
      (node (ref "D_ESC") (pin "2") (pinfunction "A_2") (pintype "unspecified"))
      (node (ref "ESC") (pin "1") (pinfunction "2_1") (pintype "unspecified"))
    )
    (net (code "41") (name "Net-(D_F-A)") (class "Default")
      (node (ref "D_F") (pin "2") (pinfunction "A_2") (pintype "unspecified"))
      (node (ref "F") (pin "1") (pinfunction "2_1") (pintype "unspecified"))
    )
    (net (code "42") (name "Net-(D_FN-A)") (class "Default")
      (node (ref "D_FN") (pin "2") (pinfunction "A_2") (pintype "unspecified"))
      (node (ref "FN") (pin "1") (pinfunction "2_1") (pintype "unspecified"))
    )
    (net (code "43") (name "Net-(D_G-A)") (class "Default")
      (node (ref "D_G") (pin "2") (pinfunction "A_2") (pintype "unspecified"))
      (node (ref "G") (pin "1") (pinfunction "2_1") (pintype "unspecified"))
    )
    (net (code "44") (name "Net-(D_H-A)") (class "Default")
      (node (ref "D_H") (pin "2") (pinfunction "A_2") (pintype "unspecified"))
      (node (ref "H") (pin "1") (pinfunction "2_1") (pintype "unspecified"))
    )
    (net (code "45") (name "Net-(D_I-A)") (class "Default")
      (node (ref "D_I") (pin "2") (pinfunction "A_2") (pintype "unspecified"))
      (node (ref "I") (pin "1") (pinfunction "2_1") (pintype "unspecified"))
    )
    (net (code "46") (name "Net-(D_J-A)") (class "Default")
      (node (ref "D_J") (pin "2") (pinfunction "A_2") (pintype "unspecified"))
      (node (ref "J") (pin "1") (pinfunction "2_1") (pintype "unspecified"))
    )
    (net (code "47") (name "Net-(D_K-A)") (class "Default")
      (node (ref "D_K") (pin "2") (pinfunction "A_2") (pintype "unspecified"))
      (node (ref "K") (pin "1") (pinfunction "2_1") (pintype "unspecified"))
    )
    (net (code "48") (name "Net-(D_L-A)") (class "Default")
      (node (ref "D_L") (pin "2") (pinfunction "A_2") (pintype "unspecified"))
      (node (ref "L") (pin "1") (pinfunction "2_1") (pintype "unspecified"))
    )
    (net (code "49") (name "Net-(D_LEFT-A)") (class "Default")
      (node (ref "D_LEFT") (pin "2") (pinfunction "A_2") (pintype "unspecified"))
      (node (ref "LEFT") (pin "1") (pinfunction "2_1") (pintype "unspecified"))
    )
    (net (code "50") (name "Net-(D_M-A)") (class "Default")
      (node (ref "D_M") (pin "2") (pinfunction "A_2") (pintype "unspecified"))
      (node (ref "M") (pin "1") (pinfunction "2_1") (pintype "unspecified"))
    )
    (net (code "51") (name "Net-(D_N-A)") (class "Default")
      (node (ref "D_N") (pin "2") (pinfunction "A_2") (pintype "unspecified"))
      (node (ref "N") (pin "1") (pinfunction "2_1") (pintype "unspecified"))
    )
    (net (code "52") (name "Net-(D_O-A)") (class "Default")
      (node (ref "D_O") (pin "2") (pinfunction "A_2") (pintype "unspecified"))
      (node (ref "O") (pin "1") (pinfunction "2_1") (pintype "unspecified"))
    )
    (net (code "53") (name "Net-(D_P-A)") (class "Default")
      (node (ref "D_P") (pin "2") (pinfunction "A_2") (pintype "unspecified"))
      (node (ref "P") (pin "1") (pinfunction "2_1") (pintype "unspecified"))
    )
    (net (code "54") (name "Net-(D_Q-A)") (class "Default")
      (node (ref "D_Q") (pin "2") (pinfunction "A_2") (pintype "unspecified"))
      (node (ref "Q") (pin "1") (pinfunction "2_1") (pintype "unspecified"))
    )
    (net (code "55") (name "Net-(D_R-A)") (class "Default")
      (node (ref "D_R") (pin "2") (pinfunction "A_2") (pintype "unspecified"))
      (node (ref "R") (pin "1") (pinfunction "2_1") (pintype "unspecified"))
    )
    (net (code "56") (name "Net-(D_RIGHT-A)") (class "Default")
      (node (ref "D_RIGHT") (pin "2") (pinfunction "A_2") (pintype "unspecified"))
      (node (ref "RIGHT") (pin "1") (pinfunction "2_1") (pintype "unspecified"))
    )
    (net (code "57") (name "Net-(D_S-A)") (class "Default")
      (node (ref "D_S") (pin "2") (pinfunction "A_2") (pintype "unspecified"))
      (node (ref "S") (pin "1") (pinfunction "2_1") (pintype "unspecified"))
    )
    (net (code "58") (name "Net-(D_SHIFT-A)") (class "Default")
      (node (ref "D_SHIFT") (pin "2") (pinfunction "A_2") (pintype "unspecified"))
      (node (ref "SHIFT") (pin "1") (pinfunction "2_1") (pintype "unspecified"))
    )
    (net (code "59") (name "Net-(D_SHIFT2-A)") (class "Default")
      (node (ref "D_SHIFT2") (pin "2") (pinfunction "A_2") (pintype "unspecified"))
      (node (ref "SHIFT2") (pin "1") (pinfunction "2_1") (pintype "unspecified"))
    )
    (net (code "60") (name "Net-(D_SPACE-A)") (class "Default")
      (node (ref "D_SPACE") (pin "2") (pinfunction "A_2") (pintype "unspecified"))
      (node (ref "SPACE") (pin "1") (pinfunction "2_1") (pintype "unspecified"))
    )
    (net (code "61") (name "Net-(D_SPACE2-A)") (class "Default")
      (node (ref "D_SPACE2") (pin "2") (pinfunction "A_2") (pintype "unspecified"))
      (node (ref "SPACE2") (pin "1") (pinfunction "2_1") (pintype "unspecified"))
    )
    (net (code "62") (name "Net-(D_T-A)") (class "Default")
      (node (ref "D_T") (pin "2") (pinfunction "A_2") (pintype "unspecified"))
      (node (ref "T") (pin "1") (pinfunction "2_1") (pintype "unspecified"))
    )
    (net (code "63") (name "Net-(D_TAB-A)") (class "Default")
      (node (ref "D_TAB") (pin "2") (pinfunction "A_2") (pintype "unspecified"))
      (node (ref "TAB") (pin "1") (pinfunction "2_1") (pintype "unspecified"))
    )
    (net (code "64") (name "Net-(D_U-A)") (class "Default")
      (node (ref "D_U") (pin "2") (pinfunction "A_2") (pintype "unspecified"))
      (node (ref "U") (pin "1") (pinfunction "2_1") (pintype "unspecified"))
    )
    (net (code "65") (name "Net-(D_UP-A)") (class "Default")
      (node (ref "D_UP") (pin "2") (pinfunction "A_2") (pintype "unspecified"))
      (node (ref "UP") (pin "1") (pinfunction "2_1") (pintype "unspecified"))
    )
    (net (code "66") (name "Net-(D_V-A)") (class "Default")
      (node (ref "D_V") (pin "2") (pinfunction "A_2") (pintype "unspecified"))
      (node (ref "V") (pin "1") (pinfunction "2_1") (pintype "unspecified"))
    )
    (net (code "67") (name "Net-(D_W-A)") (class "Default")
      (node (ref "D_W") (pin "2") (pinfunction "A_2") (pintype "unspecified"))
      (node (ref "W") (pin "1") (pinfunction "2_1") (pintype "unspecified"))
    )
    (net (code "68") (name "Net-(D_WIN-A)") (class "Default")
      (node (ref "D_WIN") (pin "2") (pinfunction "A_2") (pintype "unspecified"))
      (node (ref "WIN") (pin "1") (pinfunction "2_1") (pintype "unspecified"))
    )
    (net (code "69") (name "Net-(D_X-A)") (class "Default")
      (node (ref "D_X") (pin "2") (pinfunction "A_2") (pintype "unspecified"))
      (node (ref "X") (pin "1") (pinfunction "2_1") (pintype "unspecified"))
    )
    (net (code "70") (name "Net-(D_Y-A)") (class "Default")
      (node (ref "D_Y") (pin "2") (pinfunction "A_2") (pintype "unspecified"))
      (node (ref "Y") (pin "1") (pinfunction "2_1") (pintype "unspecified"))
    )
    (net (code "71") (name "Net-(D_Z-A)") (class "Default")
      (node (ref "D_Z") (pin "2") (pinfunction "A_2") (pintype "unspecified"))
      (node (ref "Z") (pin "1") (pinfunction "2_1") (pintype "unspecified"))
    )
    (net (code "72") (name "Net-(D_\\-A)") (class "Default")
      (node (ref "D_\\") (pin "2") (pinfunction "A_2") (pintype "unspecified"))
      (node (ref "\\") (pin "1") (pinfunction "2_1") (pintype "unspecified"))
    )
    (net (code "73") (name "Net-(D_{-A)") (class "Default")
      (node (ref "D_{") (pin "2") (pinfunction "A_2") (pintype "unspecified"))
      (node (ref "{") (pin "1") (pinfunction "2_1") (pintype "unspecified"))
    )
    (net (code "74") (name "Net-(D_}-A)") (class "Default")
      (node (ref "D_}") (pin "2") (pinfunction "A_2") (pintype "unspecified"))
      (node (ref "}") (pin "1") (pinfunction "2_1") (pintype "unspecified"))
    )
    (net (code "75") (name "ROW0") (class "Default")
      (node (ref "D_1") (pin "1") (pinfunction "C_1") (pintype "unspecified"))
      (node (ref "D_2") (pin "1") (pinfunction "C_1") (pintype "unspecified"))
      (node (ref "D_3") (pin "1") (pinfunction "C_1") (pintype "unspecified"))
      (node (ref "D_4") (pin "1") (pinfunction "C_1") (pintype "unspecified"))
      (node (ref "D_5") (pin "1") (pinfunction "C_1") (pintype "unspecified"))
      (node (ref "D_6") (pin "1") (pinfunction "C_1") (pintype "unspecified"))
      (node (ref "D_7") (pin "1") (pinfunction "C_1") (pintype "unspecified"))
      (node (ref "D_ESC") (pin "1") (pinfunction "C_1") (pintype "unspecified"))
      (node (ref "U1") (pin "20") (pinfunction "A3_20") (pintype "unspecified"))
    )
    (net (code "76") (name "ROW1") (class "Default")
      (node (ref "D_E") (pin "1") (pinfunction "C_1") (pintype "unspecified"))
      (node (ref "D_Q") (pin "1") (pinfunction "C_1") (pintype "unspecified"))
      (node (ref "D_R") (pin "1") (pinfunction "C_1") (pintype "unspecified"))
      (node (ref "D_T") (pin "1") (pinfunction "C_1") (pintype "unspecified"))
      (node (ref "D_TAB") (pin "1") (pinfunction "C_1") (pintype "unspecified"))
      (node (ref "D_U") (pin "1") (pinfunction "C_1") (pintype "unspecified"))
      (node (ref "D_W") (pin "1") (pinfunction "C_1") (pintype "unspecified"))
      (node (ref "D_Z") (pin "1") (pinfunction "C_1") (pintype "unspecified"))
      (node (ref "U1") (pin "19") (pinfunction "A2_19") (pintype "unspecified"))
    )
    (net (code "77") (name "ROW2") (class "Default")
      (node (ref "D_A") (pin "1") (pinfunction "C_1") (pintype "unspecified"))
      (node (ref "D_CAPS") (pin "1") (pinfunction "C_1") (pintype "unspecified"))
      (node (ref "D_D") (pin "1") (pinfunction "C_1") (pintype "unspecified"))
      (node (ref "D_F") (pin "1") (pinfunction "C_1") (pintype "unspecified"))
      (node (ref "D_G") (pin "1") (pinfunction "C_1") (pintype "unspecified"))
      (node (ref "D_H") (pin "1") (pinfunction "C_1") (pintype "unspecified"))
      (node (ref "D_J") (pin "1") (pinfunction "C_1") (pintype "unspecified"))
      (node (ref "D_S") (pin "1") (pinfunction "C_1") (pintype "unspecified"))
      (node (ref "U1") (pin "18") (pinfunction "A1_18") (pintype "unspecified"))
    )
    (net (code "78") (name "ROW3") (class "Default")
      (node (ref "D_B") (pin "1") (pinfunction "C_1") (pintype "unspecified"))
      (node (ref "D_C") (pin "1") (pinfunction "C_1") (pintype "unspecified"))
      (node (ref "D_M") (pin "1") (pinfunction "C_1") (pintype "unspecified"))
      (node (ref "D_N") (pin "1") (pinfunction "C_1") (pintype "unspecified"))
      (node (ref "D_SHIFT") (pin "1") (pinfunction "C_1") (pintype "unspecified"))
      (node (ref "D_V") (pin "1") (pinfunction "C_1") (pintype "unspecified"))
      (node (ref "D_X") (pin "1") (pinfunction "C_1") (pintype "unspecified"))
      (node (ref "D_Y") (pin "1") (pinfunction "C_1") (pintype "unspecified"))
      (node (ref "U1") (pin "17") (pinfunction "A0_17") (pintype "unspecified"))
    )
    (net (code "79") (name "ROW4") (class "Default")
      (node (ref "D_ALT") (pin "1") (pinfunction "C_1") (pintype "unspecified"))
      (node (ref "D_ALTGR") (pin "1") (pinfunction "C_1") (pintype "unspecified"))
      (node (ref "D_CTRL") (pin "1") (pinfunction "C_1") (pintype "unspecified"))
      (node (ref "D_CTRL2") (pin "1") (pinfunction "C_1") (pintype "unspecified"))
      (node (ref "D_FN") (pin "1") (pinfunction "C_1") (pintype "unspecified"))
      (node (ref "D_SPACE") (pin "1") (pinfunction "C_1") (pintype "unspecified"))
      (node (ref "D_SPACE2") (pin "1") (pinfunction "C_1") (pintype "unspecified"))
      (node (ref "D_WIN") (pin "1") (pinfunction "C_1") (pintype "unspecified"))
      (node (ref "U1") (pin "16") (pinfunction "15-SCLK_16") (pintype "unspecified"))
    )
    (net (code "80") (name "ROW5") (class "Default")
      (node (ref "D_-") (pin "1") (pinfunction "C_1") (pintype "unspecified"))
      (node (ref "D_0") (pin "1") (pinfunction "C_1") (pintype "unspecified"))
      (node (ref "D_8") (pin "1") (pinfunction "C_1") (pintype "unspecified"))
      (node (ref "D_9") (pin "1") (pinfunction "C_1") (pintype "unspecified"))
      (node (ref "D_BACK") (pin "1") (pinfunction "C_1") (pintype "unspecified"))
      (node (ref "D_I") (pin "1") (pinfunction "C_1") (pintype "unspecified"))
      (node (ref "D_O") (pin "1") (pinfunction "C_1") (pintype "unspecified"))
      (node (ref "D_P") (pin "1") (pinfunction "C_1") (pintype "unspecified"))
      (node (ref "U1") (pin "15") (pinfunction "14-MISO_15") (pintype "unspecified"))
    )
    (net (code "81") (name "ROW6") (class "Default")
      (node (ref "D_'") (pin "1") (pinfunction "C_1") (pintype "unspecified"))
      (node (ref "D_;") (pin "1") (pinfunction "C_1") (pintype "unspecified"))
      (node (ref "D_ENTER") (pin "1") (pinfunction "C_1") (pintype "unspecified"))
      (node (ref "D_K") (pin "1") (pinfunction "C_1") (pintype "unspecified"))
      (node (ref "D_L") (pin "1") (pinfunction "C_1") (pintype "unspecified"))
      (node (ref "D_\\") (pin "1") (pinfunction "C_1") (pintype "unspecified"))
      (node (ref "D_{") (pin "1") (pinfunction "C_1") (pintype "unspecified"))
      (node (ref "D_}") (pin "1") (pinfunction "C_1") (pintype "unspecified"))
      (node (ref "U1") (pin "14") (pinfunction "16-MOSI_14") (pintype "unspecified"))
    )
    (net (code "82") (name "ROW7") (class "Default")
      (node (ref "D_,") (pin "1") (pinfunction "C_1") (pintype "unspecified"))
      (node (ref "D_.") (pin "1") (pinfunction "C_1") (pintype "unspecified"))
      (node (ref "D_/") (pin "1") (pinfunction "C_1") (pintype "unspecified"))
      (node (ref "D_DOWN") (pin "1") (pinfunction "C_1") (pintype "unspecified"))
      (node (ref "D_LEFT") (pin "1") (pinfunction "C_1") (pintype "unspecified"))
      (node (ref "D_RIGHT") (pin "1") (pinfunction "C_1") (pintype "unspecified"))
      (node (ref "D_SHIFT2") (pin "1") (pinfunction "C_1") (pintype "unspecified"))
      (node (ref "D_UP") (pin "1") (pinfunction "C_1") (pintype "unspecified"))
      (node (ref "U1") (pin "13") (pinfunction "10-A10_13") (pintype "unspecified"))
    )
    (net (code "83") (name "RST") (class "Default")
      (node (ref "RST") (pin "1") (pinfunction "1_1") (pintype "unspecified"))
      (node (ref "U1") (pin "22") (pinfunction "RST_22") (pintype "unspecified"))
    )
    (net (code "84") (name "SCL") (class "Default")
      (node (ref "PCB1") (pin "3") (pinfunction "SCL_3") (pintype "passive"))
      (node (ref "U1") (pin "6") (pinfunction "3-SCL_6") (pintype "unspecified"))
    )
    (net (code "85") (name "SDA") (class "Default")
      (node (ref "PCB1") (pin "4") (pinfunction "SDA_4") (pintype "passive"))
      (node (ref "U1") (pin "5") (pinfunction "2-SDA_5") (pintype "unspecified"))
    )
    (net (code "86") (name "VCC") (class "Default")
      (node (ref "PCB1") (pin "2") (pinfunction "VCC_2") (pintype "input"))
      (node (ref "U1") (pin "21") (pinfunction "Vcc_21") (pintype "unspecified"))
    )
  )
)
